# DAPLink-HS.net
KiCad netlist of a schematic drawn in EasyEDA Pro
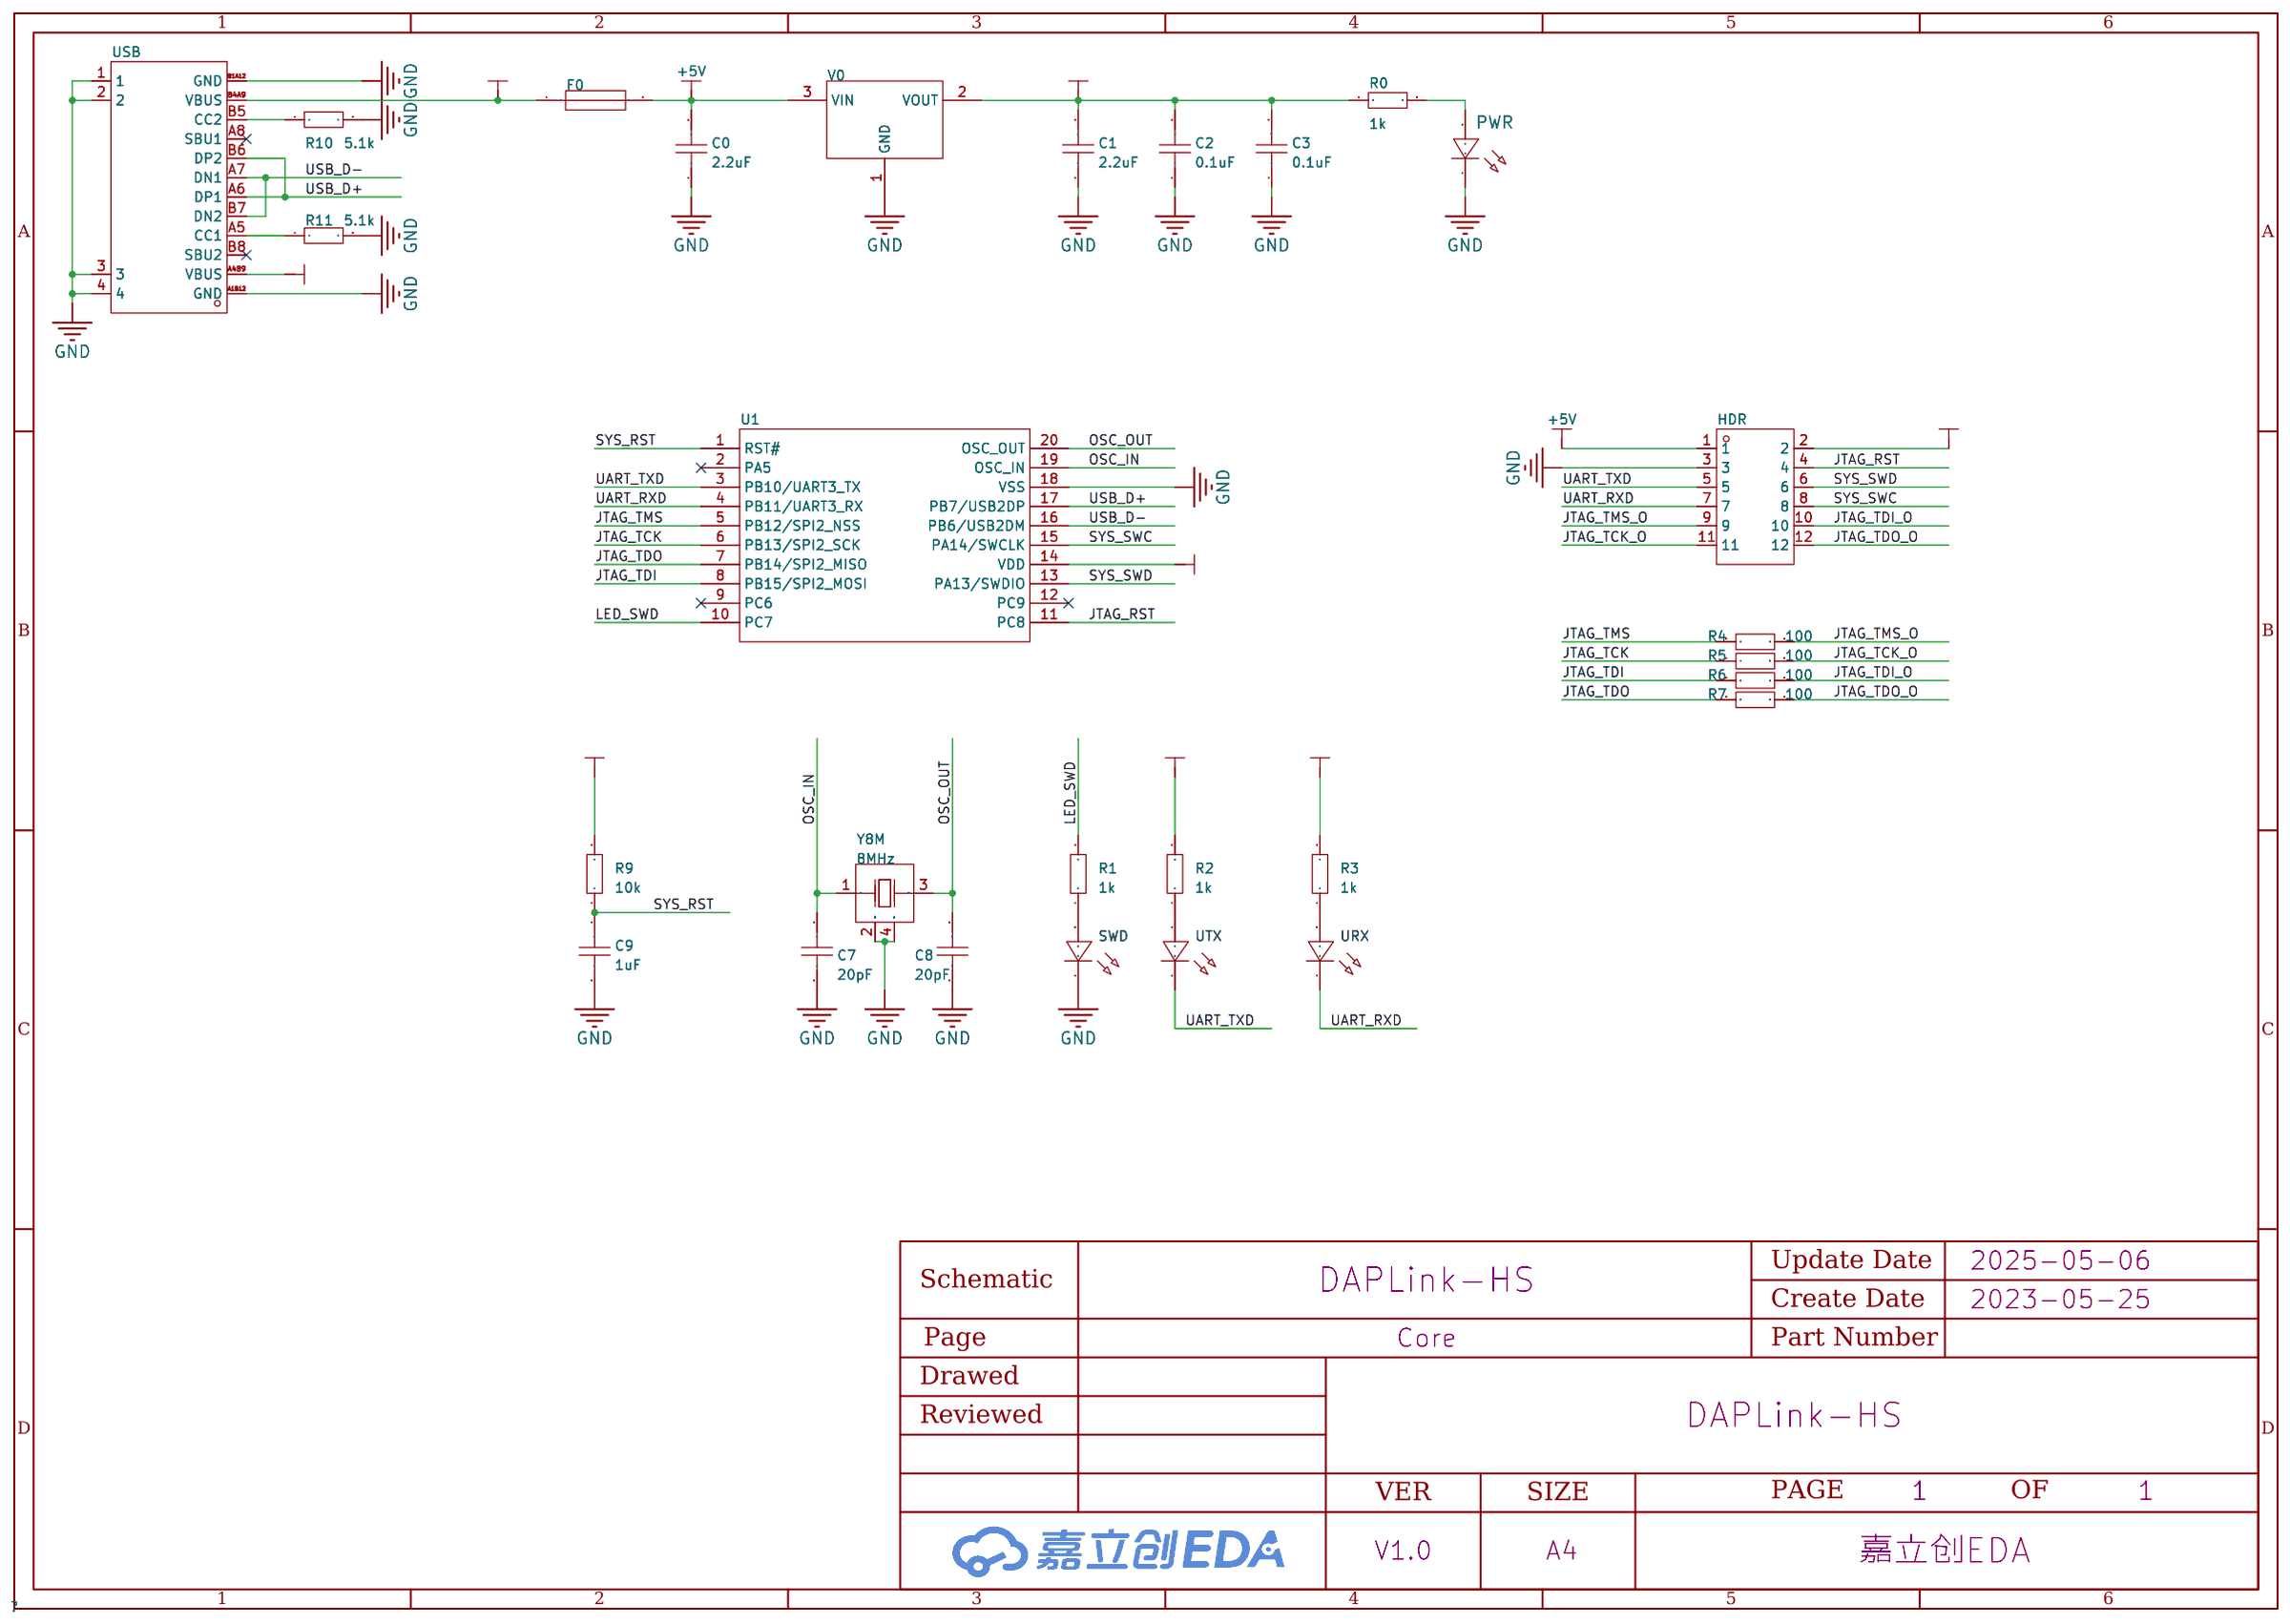
[diagram p0: schematic sheet]

(export (version "E")
  (design (tool "Eeschema 10.0.6"))
  (components
    (comp (ref "C0")
      (value "2.2uF")
      (footprint "easyedapro:C0603")
      (description "容值:100nF;精度:±10%;额定电压:50V;温度系数:X7R;")
      (libsource (lib "easyedapro") (part "C1210X7R475K630NT"))
    )
    (comp (ref "C1")
      (value "2.2uF")
      (footprint "easyedapro:C0603")
      (description "容值:100nF;精度:±10%;额定电压:50V;温度系数:X7R;")
      (libsource (lib "easyedapro") (part "C1210X7R475K630NT"))
    )
    (comp (ref "C2")
      (value "0.1uF")
      (footprint "easyedapro:C0603")
      (description "容值:100nF;精度:±10%;额定电压:50V;温度系数:X7R;")
      (libsource (lib "easyedapro") (part "C1210X7R475K630NT"))
    )
    (comp (ref "C3")
      (value "0.1uF")
      (footprint "easyedapro:C0603")
      (description "容值:100nF;精度:±10%;额定电压:50V;温度系数:X7R;")
      (libsource (lib "easyedapro") (part "C1210X7R475K630NT"))
    )
    (comp (ref "C7")
      (value "20pF")
      (footprint "easyedapro:C0603")
      (description "容值:100nF;精度:±10%;额定电压:50V;温度系数:X7R;")
      (libsource (lib "easyedapro") (part "C1210X7R475K630NT"))
    )
    (comp (ref "C8")
      (value "20pF")
      (footprint "easyedapro:C0603")
      (description "容值:100nF;精度:±10%;额定电压:50V;温度系数:X7R;")
      (libsource (lib "easyedapro") (part "C1210X7R475K630NT"))
    )
    (comp (ref "C9")
      (value "1uF")
      (footprint "easyedapro:C0603")
      (description "容值:100nF;精度:±10%;额定电压:50V;温度系数:X7R;")
      (libsource (lib "easyedapro") (part "C1210X7R475K630NT"))
    )
    (comp (ref "F0")
      (value "JK-nSMD050-30")
      (footprint "easyedapro:F1206")
      (description "耐压:30V;最大电流:100A;保持电流(Ih):500mA;跳闸电流:1A;")
      (fields (field (name "Manufacturer") "JK(金科)"))
      (libsource (lib "easyedapro") (part "JK-NSMD050-30V"))
    )
    (comp (ref "HDR")
      (value "~")
      (footprint "easyedapro:HDR-SMD_2X6P-P2.54")
      (libsource (lib "easyedapro") (part "HDR-M-2.54_2x6"))
    )
    (comp (ref "PWR")
      (value "~")
      (footprint "easyedapro:LED0603-RD_BLUE")
      (libsource (lib "easyedapro") (part "LED_R"))
    )
    (comp (ref "R0") (value "1k") (footprint "easyedapro:R0603") (libsource (lib "easyedapro") (part "电阻")))
    (comp (ref "R1") (value "1k") (footprint "easyedapro:R0603") (libsource (lib "easyedapro") (part "电阻")))
    (comp (ref "R2") (value "1k") (footprint "easyedapro:R0603") (libsource (lib "easyedapro") (part "电阻")))
    (comp (ref "R3") (value "1k") (footprint "easyedapro:R0603") (libsource (lib "easyedapro") (part "电阻")))
    (comp (ref "R4") (value "100") (footprint "easyedapro:R0603") (libsource (lib "easyedapro") (part "电阻")))
    (comp (ref "R5") (value "100") (footprint "easyedapro:R0603") (libsource (lib "easyedapro") (part "电阻")))
    (comp (ref "R6") (value "100") (footprint "easyedapro:R0603") (libsource (lib "easyedapro") (part "电阻")))
    (comp (ref "R7") (value "100") (footprint "easyedapro:R0603") (libsource (lib "easyedapro") (part "电阻")))
    (comp (ref "R9") (value "10k") (footprint "easyedapro:R0603") (libsource (lib "easyedapro") (part "电阻")))
    (comp (ref "R10")
      (value "5.1k")
      (footprint "easyedapro:R0603")
      (libsource (lib "easyedapro") (part "电阻"))
    )
    (comp (ref "R11")
      (value "5.1k")
      (footprint "easyedapro:R0603")
      (libsource (lib "easyedapro") (part "电阻"))
    )
    (comp (ref "SWD")
      (value "~")
      (footprint "easyedapro:LED_0603")
      (libsource (lib "easyedapro") (part "LED_G"))
    )
    (comp (ref "U1")
      (value "~")
      (footprint "easyedapro:TSSOP-20_L6.5-W4.4-P0.65-LS6.4-BL")
      (libsource (lib "easyedapro") (part "CH32V305FBP6"))
    )
    (comp (ref "URX")
      (value "~")
      (footprint "easyedapro:LED_0603")
      (libsource (lib "easyedapro") (part "LED_B"))
    )
    (comp (ref "USB")
      (value "USB-TYPE-C-017")
      (footprint "easyedapro:USB-TYPE-C-SMD_C9900008089")
      (description "连接器类型:Type-C;标准:-;公母:母座;触点数量:16;端口数量:1;安装方式:卧贴;额定电流 - 电源:3A;工作温度范围:-25~+85;")
      (fields (field (name "Manufacturer") "DEALON(德艺隆)"))
      (libsource (lib "easyedapro") (part "USB-TYPE-C-017"))
    )
    (comp (ref "UTX")
      (value "~")
      (footprint "easyedapro:LED_0603")
      (libsource (lib "easyedapro") (part "LED_B"))
    )
    (comp (ref "V0")
      (value "HT7233")
      (footprint "easyedapro:SOT-23-3_L2.9-W1.6-P1.90-LS2.8-BR")
      (description "输出类型:固定;最大输入电压:8V;输出电压:3.3V;最大输出电流:300mA;电源纹波抑制比(PSRR):-;输出极性:正极;")
      (fields (field (name "Manufacturer") "HOLTEK(合泰/盛群)"))
      (libsource (lib "easyedapro") (part "HT7233"))
    )
    (comp (ref "Y8M")
      (value "8MHz")
      (footprint "easyedapro:OSC-SMD_4P-L3.2-W2.5-BL")
      (description "晶振类型:贴片无源晶振;频率:12MHz;频率公差:±10ppm;频率稳定度:±30ppm;负载电容:20pF;工作温度:-40~+85;")
      (fields (field (name "Manufacturer Part") "X322512MSB4SI") (field (name "Manufacturer") "YXC(扬兴晶振)"))
      (libsource (lib "easyedapro") (part "X322512MSB4SI"))
    )
  )
  (nets
    (net (code "1") (name "+3.3V") (class "Default")
      (node (ref "C1") (pin "2") (pinfunction "2_2") (pintype "input"))
      (node (ref "C2") (pin "2") (pinfunction "2_2") (pintype "input"))
      (node (ref "C3") (pin "2") (pinfunction "2_2") (pintype "input"))
      (node (ref "HDR") (pin "2") (pinfunction "2_2") (pintype "input"))
      (node (ref "R0") (pin "1") (pinfunction "1_1") (pintype "input"))
      (node (ref "R2") (pin "2") (pinfunction "2_2") (pintype "input"))
      (node (ref "R3") (pin "2") (pinfunction "2_2") (pintype "input"))
      (node (ref "R9") (pin "2") (pinfunction "2_2") (pintype "input"))
      (node (ref "U1") (pin "14") (pinfunction "VDD_14") (pintype "input"))
      (node (ref "V0") (pin "2") (pinfunction "VOUT_2") (pintype "unspecified"))
    )
    (net (code "2") (name "+5V") (class "Default")
      (node (ref "C0") (pin "2") (pinfunction "2_2") (pintype "input"))
      (node (ref "F0") (pin "2") (pinfunction "2_2") (pintype "unspecified"))
      (node (ref "HDR") (pin "1") (pinfunction "1_1") (pintype "input"))
      (node (ref "V0") (pin "3") (pinfunction "VIN_3") (pintype "unspecified"))
    )
    (net (code "3") (name "/JTAG_RST") (class "Default")
      (node (ref "HDR") (pin "4") (pinfunction "4_4") (pintype "input"))
      (node (ref "U1") (pin "11") (pinfunction "PC8_11") (pintype "input"))
    )
    (net (code "4") (name "/JTAG_TCK") (class "Default")
      (node (ref "R5") (pin "1") (pinfunction "1_1") (pintype "input"))
      (node (ref "U1") (pin "6") (pinfunction "PB13/SPI2_SCK_6") (pintype "input"))
    )
    (net (code "5") (name "/JTAG_TCK_O") (class "Default")
      (node (ref "HDR") (pin "11") (pinfunction "11_11") (pintype "input"))
      (node (ref "R5") (pin "2") (pinfunction "2_2") (pintype "input"))
    )
    (net (code "6") (name "/JTAG_TDI") (class "Default")
      (node (ref "R6") (pin "1") (pinfunction "1_1") (pintype "input"))
      (node (ref "U1") (pin "8") (pinfunction "PB15/SPI2_MOSI_8") (pintype "input"))
    )
    (net (code "7") (name "/JTAG_TDI_O") (class "Default")
      (node (ref "HDR") (pin "10") (pinfunction "10_10") (pintype "input"))
      (node (ref "R6") (pin "2") (pinfunction "2_2") (pintype "input"))
    )
    (net (code "8") (name "/JTAG_TDO") (class "Default")
      (node (ref "R7") (pin "1") (pinfunction "1_1") (pintype "input"))
      (node (ref "U1") (pin "7") (pinfunction "PB14/SPI2_MISO_7") (pintype "input"))
    )
    (net (code "9") (name "/JTAG_TDO_O") (class "Default")
      (node (ref "HDR") (pin "12") (pinfunction "12_12") (pintype "input"))
      (node (ref "R7") (pin "2") (pinfunction "2_2") (pintype "input"))
    )
    (net (code "10") (name "/JTAG_TMS") (class "Default")
      (node (ref "R4") (pin "1") (pinfunction "1_1") (pintype "input"))
      (node (ref "U1") (pin "5") (pinfunction "PB12/SPI2_NSS_5") (pintype "input"))
    )
    (net (code "11") (name "/JTAG_TMS_O") (class "Default")
      (node (ref "HDR") (pin "9") (pinfunction "9_9") (pintype "input"))
      (node (ref "R4") (pin "2") (pinfunction "2_2") (pintype "input"))
    )
    (net (code "12") (name "/LED_SWD") (class "Default")
      (node (ref "R1") (pin "2") (pinfunction "2_2") (pintype "input"))
      (node (ref "U1") (pin "10") (pinfunction "PC7_10") (pintype "input"))
    )
    (net (code "13") (name "/OSC_IN") (class "Default")
      (node (ref "C7") (pin "1") (pinfunction "1_1") (pintype "input"))
      (node (ref "U1") (pin "19") (pinfunction "OSC_IN_19") (pintype "input"))
      (node (ref "Y8M") (pin "1") (pinfunction "OSC1_1") (pintype "input"))
    )
    (net (code "14") (name "/OSC_OUT") (class "Default")
      (node (ref "C8") (pin "2") (pinfunction "2_2") (pintype "input"))
      (node (ref "U1") (pin "20") (pinfunction "OSC_OUT_20") (pintype "input"))
      (node (ref "Y8M") (pin "3") (pinfunction "OSC2_3") (pintype "input"))
    )
    (net (code "15") (name "/SYS_RST") (class "Default")
      (node (ref "C9") (pin "1") (pinfunction "1_1") (pintype "input"))
      (node (ref "R9") (pin "1") (pinfunction "1_1") (pintype "input"))
      (node (ref "U1") (pin "1") (pinfunction "RST#_1") (pintype "input"))
    )
    (net (code "16") (name "/SYS_SWC") (class "Default")
      (node (ref "HDR") (pin "8") (pinfunction "8_8") (pintype "input"))
      (node (ref "U1") (pin "15") (pinfunction "PA14/SWCLK_15") (pintype "input"))
    )
    (net (code "17") (name "/SYS_SWD") (class "Default")
      (node (ref "HDR") (pin "6") (pinfunction "6_6") (pintype "input"))
      (node (ref "U1") (pin "13") (pinfunction "PA13/SWDIO_13") (pintype "input"))
    )
    (net (code "18") (name "/UART_RXD") (class "Default")
      (node (ref "HDR") (pin "7") (pinfunction "7_7") (pintype "input"))
      (node (ref "U1") (pin "4") (pinfunction "PB11/UART3_RX_4") (pintype "input"))
      (node (ref "URX") (pin "1") (pinfunction "C_1") (pintype "input"))
    )
    (net (code "19") (name "/UART_TXD") (class "Default")
      (node (ref "HDR") (pin "5") (pinfunction "5_5") (pintype "input"))
      (node (ref "U1") (pin "3") (pinfunction "PB10/UART3_TX_3") (pintype "input"))
      (node (ref "UTX") (pin "1") (pinfunction "C_1") (pintype "input"))
    )
    (net (code "20") (name "/USB_D+") (class "Default")
      (node (ref "U1") (pin "17") (pinfunction "PB7/USB2DP_17") (pintype "input"))
      (node (ref "USB") (pin "A6") (pinfunction "DP1_A6") (pintype "input"))
      (node (ref "USB") (pin "B6") (pinfunction "DP2_B6") (pintype "input"))
    )
    (net (code "21") (name "/USB_D-") (class "Default")
      (node (ref "U1") (pin "16") (pinfunction "PB6/USB2DM_16") (pintype "input"))
      (node (ref "USB") (pin "A7") (pinfunction "DN1_A7") (pintype "input"))
      (node (ref "USB") (pin "B7") (pinfunction "DN2_B7") (pintype "input"))
    )
    (net (code "22") (name "GND") (class "Default")
      (node (ref "C0") (pin "1") (pinfunction "1_1") (pintype "input"))
      (node (ref "C1") (pin "1") (pinfunction "1_1") (pintype "input"))
      (node (ref "C2") (pin "1") (pinfunction "1_1") (pintype "input"))
      (node (ref "C3") (pin "1") (pinfunction "1_1") (pintype "input"))
      (node (ref "C7") (pin "2") (pinfunction "2_2") (pintype "input"))
      (node (ref "C8") (pin "1") (pinfunction "1_1") (pintype "input"))
      (node (ref "C9") (pin "2") (pinfunction "2_2") (pintype "input"))
      (node (ref "HDR") (pin "3") (pinfunction "3_3") (pintype "input"))
      (node (ref "PWR") (pin "1") (pinfunction "C_1") (pintype "input"))
      (node (ref "R10") (pin "2") (pinfunction "2_2") (pintype "input"))
      (node (ref "R11") (pin "2") (pinfunction "2_2") (pintype "input"))
      (node (ref "SWD") (pin "1") (pinfunction "C_1") (pintype "input"))
      (node (ref "U1") (pin "18") (pinfunction "VSS_18") (pintype "input"))
      (node (ref "USB") (pin "1") (pinfunction "1_1") (pintype "input"))
      (node (ref "USB") (pin "2") (pinfunction "2_2") (pintype "input"))
      (node (ref "USB") (pin "3") (pinfunction "3_3") (pintype "input"))
      (node (ref "USB") (pin "4") (pinfunction "4_4") (pintype "input"))
      (node (ref "USB") (pin "A1B12") (pinfunction "GND_A1B12") (pintype "input"))
      (node (ref "USB") (pin "B1A12") (pinfunction "GND_B1A12") (pintype "input"))
      (node (ref "V0") (pin "1") (pinfunction "GND_1") (pintype "unspecified"))
      (node (ref "Y8M") (pin "2") (pinfunction "GND_2") (pintype "input"))
      (node (ref "Y8M") (pin "4") (pinfunction "GND_4") (pintype "input"))
    )
    (net (code "23") (name "Net-(PWR-A)") (class "Default")
      (node (ref "PWR") (pin "2") (pinfunction "A_2") (pintype "input"))
      (node (ref "R0") (pin "2") (pinfunction "2_2") (pintype "input"))
    )
    (net (code "24") (name "Net-(SWD-A)") (class "Default")
      (node (ref "R1") (pin "1") (pinfunction "1_1") (pintype "input"))
      (node (ref "SWD") (pin "2") (pinfunction "A_2") (pintype "input"))
    )
    (net (code "25") (name "Net-(URX-A)") (class "Default")
      (node (ref "R3") (pin "1") (pinfunction "1_1") (pintype "input"))
      (node (ref "URX") (pin "2") (pinfunction "A_2") (pintype "input"))
    )
    (net (code "26") (name "Net-(USB-CC1)") (class "Default")
      (node (ref "R11") (pin "1") (pinfunction "1_1") (pintype "input"))
      (node (ref "USB") (pin "A5") (pinfunction "CC1_A5") (pintype "input"))
    )
    (net (code "27") (name "Net-(USB-CC2)") (class "Default")
      (node (ref "R10") (pin "1") (pinfunction "1_1") (pintype "input"))
      (node (ref "USB") (pin "B5") (pinfunction "CC2_B5") (pintype "input"))
    )
    (net (code "28") (name "Net-(UTX-A)") (class "Default")
      (node (ref "R2") (pin "1") (pinfunction "1_1") (pintype "input"))
      (node (ref "UTX") (pin "2") (pinfunction "A_2") (pintype "input"))
    )
    (net (code "29") (name "VBUS") (class "Default")
      (node (ref "F0") (pin "1") (pinfunction "1_1") (pintype "unspecified"))
      (node (ref "USB") (pin "A4B9") (pinfunction "VBUS_A4B9") (pintype "input"))
      (node (ref "USB") (pin "B4A9") (pinfunction "VBUS_B4A9") (pintype "input"))
    )
    (net (code "30") (name "unconnected-(U1-PA5-Pad2)") (class "Default")
      (node (ref "U1") (pin "2") (pinfunction "PA5_2") (pintype "input+no_connect"))
    )
    (net (code "31") (name "unconnected-(U1-PC6-Pad9)") (class "Default")
      (node (ref "U1") (pin "9") (pinfunction "PC6_9") (pintype "input+no_connect"))
    )
    (net (code "32") (name "unconnected-(U1-PC9-Pad12)") (class "Default")
      (node (ref "U1") (pin "12") (pinfunction "PC9_12") (pintype "input+no_connect"))
    )
    (net (code "33") (name "unconnected-(USB-SBU1-PadA8)") (class "Default")
      (node (ref "USB") (pin "A8") (pinfunction "SBU1_A8") (pintype "input+no_connect"))
    )
    (net (code "34") (name "unconnected-(USB-SBU2-PadB8)") (class "Default")
      (node (ref "USB") (pin "B8") (pinfunction "SBU2_B8") (pintype "input+no_connect"))
    )
  )
)
